# strobeAT10.net
KiCad netlist of a schematic drawn in EAGLE
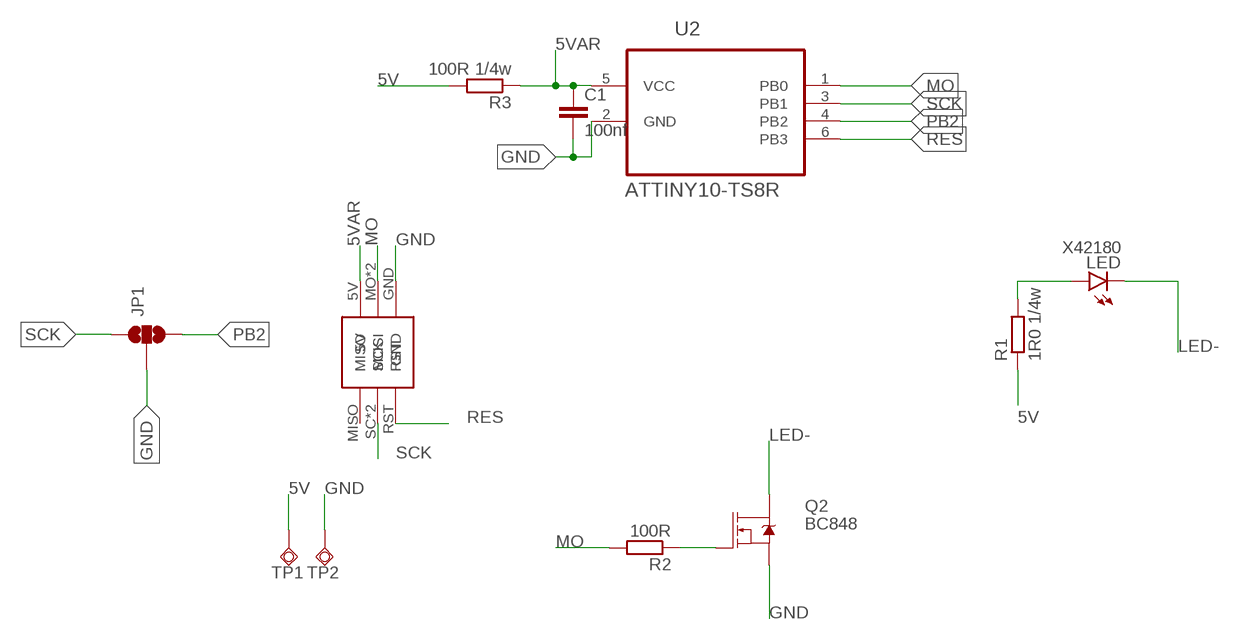
[diagram p0: schematic, sheet 1]

(export (version "E")
  (design (tool "Eeschema 10.0.6"))
  (components
    (comp (ref "C1")
      (value "100nf")
      (footprint "eagle-import:C0603")
      (libsource (lib "eagle-import") (part "C-EUC0603"))
    )
    (comp (ref "JP1")
      (value "JUMPER-SMT_3_NO_SILK")
      (footprint "eagle-import:SMT-JUMPER_3_NO_SILK")
      (libsource (lib "eagle-import") (part "JUMPER-SMT_3_NO_SILK"))
    )
    (comp (ref "LED")
      (value "X42180")
      (footprint "eagle-import:Z-POWER-LED-DOME-TYPE")
      (libsource (lib "eagle-import") (part "X42180"))
    )
    (comp (ref "Q2")
      (value "BC848")
      (footprint "eagle-import:SOT23-3")
      (libsource (lib "eagle-import") (part "MOSFET-NCH-AO3404A"))
    )
    (comp (ref "R1")
      (value "1R0 1/4w")
      (footprint "eagle-import:R0805")
      (libsource (lib "eagle-import") (part "R-EU_R0805"))
    )
    (comp (ref "R2")
      (value "100R")
      (footprint "eagle-import:R0603")
      (libsource (lib "eagle-import") (part "R-EU_R0603"))
    )
    (comp (ref "R3")
      (value "100R 1/4w")
      (footprint "eagle-import:R0805")
      (libsource (lib "eagle-import") (part "R-EU_R0805"))
    )
    (comp (ref "TP1")
      (value "TPSQPAD1-13Y")
      (footprint "eagle-import:P1-13Y")
      (libsource (lib "eagle-import") (part "TPSQPAD1-13Y"))
    )
    (comp (ref "TP2")
      (value "TPSQPAD1-13Y")
      (footprint "eagle-import:P1-13Y")
      (libsource (lib "eagle-import") (part "TPSQPAD1-13Y"))
    )
    (comp (ref "U$1")
      (value "ISCP_PORTPOGONEW")
      (footprint "eagle-import:ISCP_PADS_2ROW2HNEW")
      (libsource (lib "eagle-import") (part "ISCP_PORTPOGONEW"))
    )
    (comp (ref "U2")
      (value "ATTINY10-TS8R")
      (footprint "eagle-import:SOT95P280X145-6N")
      (fields (field (name "MF") "Microchip"))
      (libsource (lib "eagle-import") (part "ATTINY10-TS8R"))
    )
  )
  (nets
    (net (code "1") (name "/5V") (class "Default")
      (node (ref "R1") (pin "1") (pinfunction "1_1") (pintype "passive"))
      (node (ref "R3") (pin "2") (pinfunction "2_2") (pintype "passive"))
      (node (ref "TP1") (pin "TP") (pinfunction "TP_TP") (pintype "input"))
    )
    (net (code "2") (name "/5VAR") (class "Default")
      (node (ref "C1") (pin "1") (pinfunction "1_1") (pintype "passive"))
      (node (ref "R3") (pin "1") (pinfunction "1_1") (pintype "passive"))
      (node (ref "U$1") (pin "5V") (pinfunction "5V_5V") (pintype "bidirectional"))
      (node (ref "U2") (pin "5") (pinfunction "VCC_5") (pintype "power_in"))
    )
    (net (code "3") (name "/LED-") (class "Default")
      (node (ref "LED") (pin "C") (pinfunction "C_C") (pintype "passive"))
      (node (ref "Q2") (pin "3") (pinfunction "D_3") (pintype "bidirectional"))
    )
    (net (code "4") (name "GND") (class "Default")
      (node (ref "C1") (pin "2") (pinfunction "2_2") (pintype "passive"))
      (node (ref "JP1") (pin "2") (pinfunction "2_2") (pintype "passive"))
      (node (ref "Q2") (pin "2") (pinfunction "S_2") (pintype "bidirectional"))
      (node (ref "TP2") (pin "TP") (pinfunction "TP_TP") (pintype "input"))
      (node (ref "U$1") (pin "GND") (pinfunction "GND_GND") (pintype "bidirectional"))
      (node (ref "U2") (pin "2") (pinfunction "GND_2") (pintype "passive"))
    )
    (net (code "5") (name "MO") (class "Default")
      (node (ref "R2") (pin "2") (pinfunction "2_2") (pintype "passive"))
      (node (ref "U$1") (pin "MO") (pinfunction "MOSI_MO") (pintype "bidirectional"))
      (node (ref "U$1") (pin "MOSI") (pinfunction "MOSI_MOSI") (pintype "bidirectional"))
      (node (ref "U2") (pin "1") (pinfunction "PB0_1") (pintype "bidirectional"))
    )
    (net (code "6") (name "Net-(LED-PadA)") (class "Default")
      (node (ref "LED") (pin "A") (pinfunction "A_A") (pintype "passive"))
      (node (ref "R1") (pin "2") (pinfunction "2_2") (pintype "passive"))
    )
    (net (code "7") (name "Net-(Q2-G)") (class "Default")
      (node (ref "Q2") (pin "1") (pinfunction "G_1") (pintype "bidirectional"))
      (node (ref "R2") (pin "1") (pinfunction "1_1") (pintype "passive"))
    )
    (net (code "8") (name "PB2") (class "Default")
      (node (ref "JP1") (pin "3") (pinfunction "3_3") (pintype "passive"))
      (node (ref "U2") (pin "4") (pinfunction "PB2_4") (pintype "bidirectional"))
    )
    (net (code "9") (name "RES") (class "Default")
      (node (ref "U$1") (pin "RST") (pinfunction "RST_RST") (pintype "bidirectional"))
      (node (ref "U2") (pin "6") (pinfunction "PB3_6") (pintype "bidirectional"))
    )
    (net (code "10") (name "SCK") (class "Default")
      (node (ref "JP1") (pin "1") (pinfunction "1_1") (pintype "passive"))
      (node (ref "U$1") (pin "SC") (pinfunction "SCK_SC") (pintype "bidirectional"))
      (node (ref "U$1") (pin "SCK") (pinfunction "SCK_SCK") (pintype "bidirectional"))
      (node (ref "U2") (pin "3") (pinfunction "PB1_3") (pintype "bidirectional"))
    )
    (net (code "11") (name "unconnected-(U$1-PadMISO)") (class "Default")
      (node (ref "U$1") (pin "MISO") (pinfunction "MISO_MISO") (pintype "bidirectional"))
    )
  )
)
